# 1_P1_schdoc.net
KiCad netlist of a schematic drawn in Altium Designer
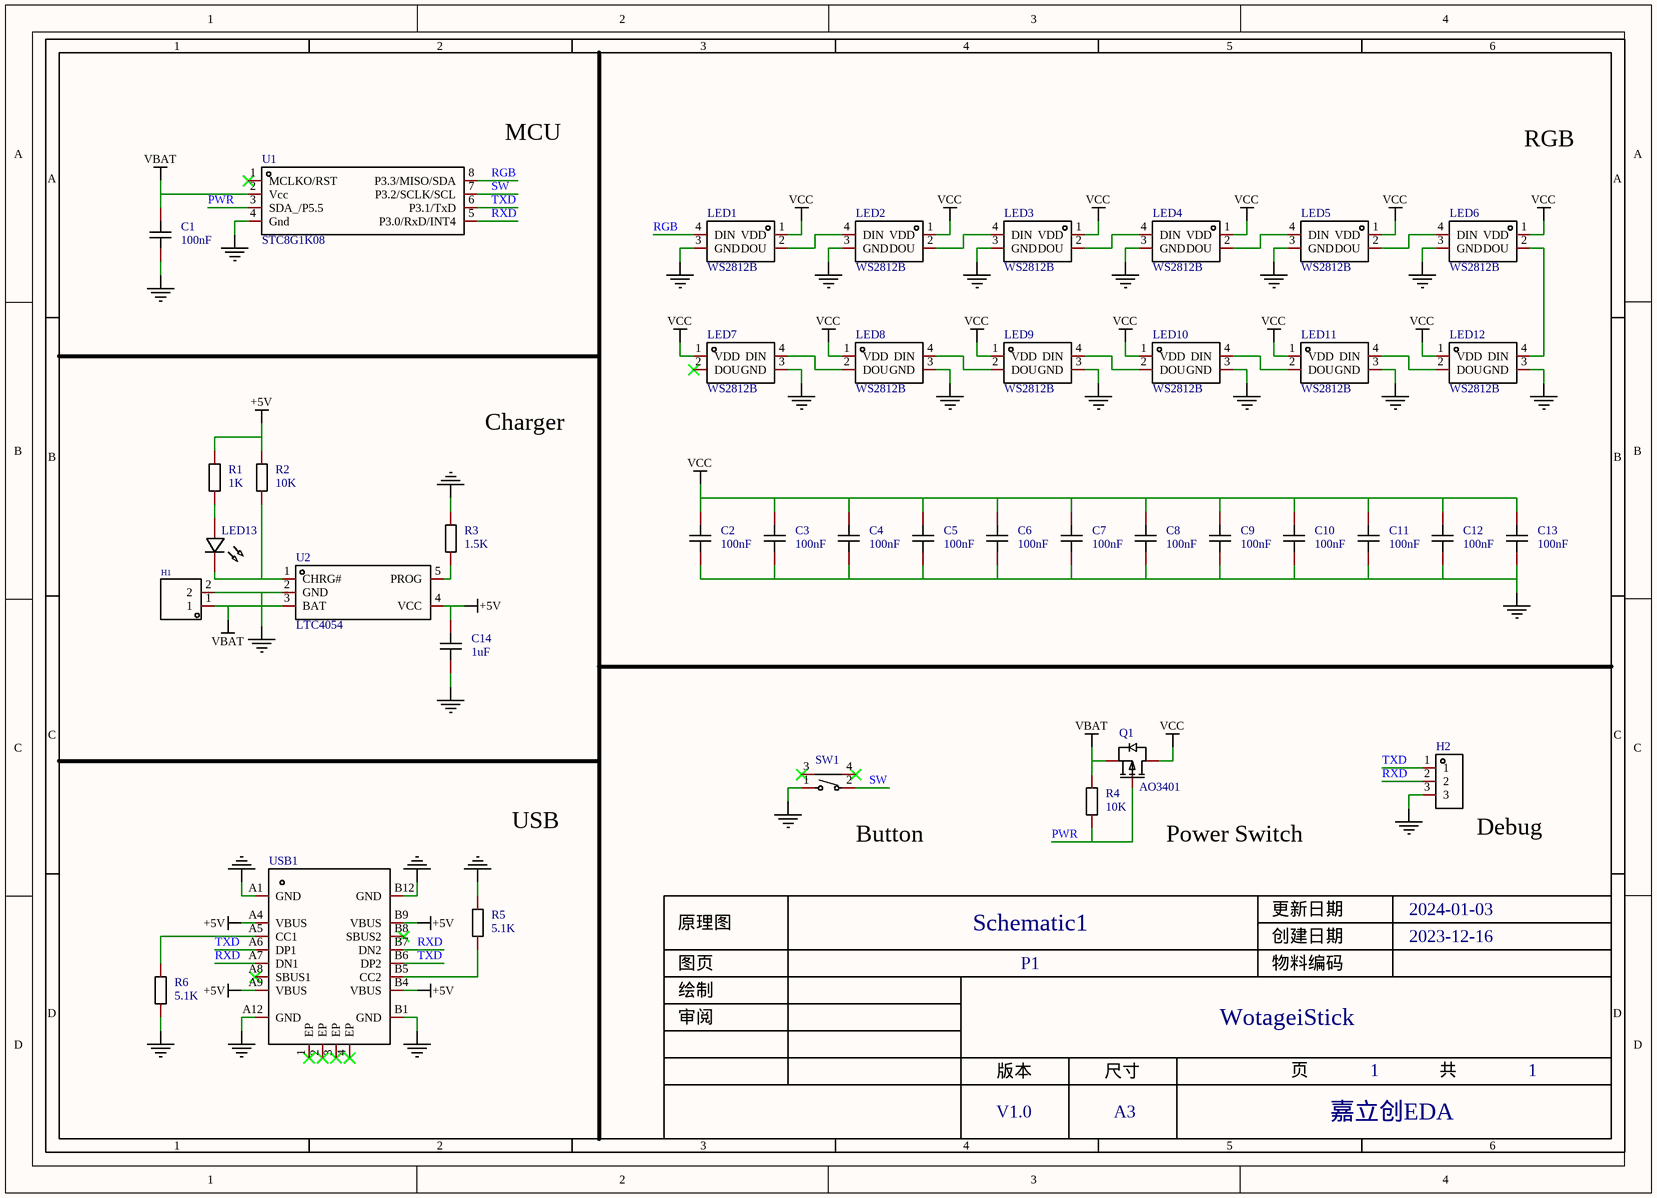
[diagram p0: 1_P1.schdoc.schdoc]

(export (version "E")
  (design (tool "Eeschema 10.0.6"))
  (components
    (comp (ref "C1")
      (value "100nF")
      (fields (field (name "NAME") "100nF"))
      (libsource (lib "altium-import") (part "root_1_CAP_0603_"))
    )
    (comp (ref "C2")
      (value "100nF")
      (fields (field (name "NAME") "100nF"))
      (libsource (lib "altium-import") (part "root_1_CAP_0603_"))
    )
    (comp (ref "C3")
      (value "100nF")
      (fields (field (name "NAME") "100nF"))
      (libsource (lib "altium-import") (part "root_1_CAP_0603_"))
    )
    (comp (ref "C4")
      (value "100nF")
      (fields (field (name "NAME") "100nF"))
      (libsource (lib "altium-import") (part "root_1_CAP_0603_"))
    )
    (comp (ref "C5")
      (value "100nF")
      (fields (field (name "NAME") "100nF"))
      (libsource (lib "altium-import") (part "root_1_CAP_0603_"))
    )
    (comp (ref "C6")
      (value "100nF")
      (fields (field (name "NAME") "100nF"))
      (libsource (lib "altium-import") (part "root_1_CAP_0603_"))
    )
    (comp (ref "C7")
      (value "100nF")
      (fields (field (name "NAME") "100nF"))
      (libsource (lib "altium-import") (part "root_1_CAP_0603_"))
    )
    (comp (ref "C8")
      (value "100nF")
      (fields (field (name "NAME") "100nF"))
      (libsource (lib "altium-import") (part "root_1_CAP_0603_"))
    )
    (comp (ref "C9")
      (value "100nF")
      (fields (field (name "NAME") "100nF"))
      (libsource (lib "altium-import") (part "root_1_CAP_0603_"))
    )
    (comp (ref "C10")
      (value "100nF")
      (fields (field (name "NAME") "100nF"))
      (libsource (lib "altium-import") (part "root_1_CAP_0603_"))
    )
    (comp (ref "C11")
      (value "100nF")
      (fields (field (name "NAME") "100nF"))
      (libsource (lib "altium-import") (part "root_1_CAP_0603_"))
    )
    (comp (ref "C12")
      (value "100nF")
      (fields (field (name "NAME") "100nF"))
      (libsource (lib "altium-import") (part "root_1_CAP_0603_"))
    )
    (comp (ref "C13")
      (value "100nF")
      (fields (field (name "NAME") "100nF"))
      (libsource (lib "altium-import") (part "root_1_CAP_0603_"))
    )
    (comp (ref "C14")
      (value "1uF")
      (fields (field (name "NAME") "1uF"))
      (libsource (lib "altium-import") (part "root_1_CAP_0603_"))
    )
    (comp (ref "H1")
      (value "HDR-M_2.54_1x2P")
      (fields (field (name "MANUFACTURER") "Ckmtw(灿科盟)") (field (name "MANUFACTURER PART") "B-2100S02P-A110"))
      (libsource (lib "altium-import") (part "root_2_HDR-M_2.54_1x2P_"))
    )
    (comp (ref "H2")
      (value "HDR-M_2.54_1x3P")
      (libsource (lib "altium-import") (part "root_0_HDR-M_2.54_1x3P_"))
    )
    (comp (ref "LED1")
      (value "WS2812B")
      (description "发光颜色:RGB三色;二极管配置:-;功率:-;透镜颜色:无色透明透镜;主波长:-;色温:-;发光角度:120°;安装方式:正贴;工作温度:-30℃~+70℃;")
      (fields (field (name "NAME") "WS2812B") (field (name "MANUFACTURER") "XINGLIGHT(成兴光)"))
      (libsource (lib "altium-import") (part "root_0_mirrored_XL-5050RGBC-WS2812B_"))
    )
    (comp (ref "LED2")
      (value "WS2812B")
      (description "发光颜色:RGB三色;二极管配置:-;功率:-;透镜颜色:无色透明透镜;主波长:-;色温:-;发光角度:120°;安装方式:正贴;工作温度:-30℃~+70℃;")
      (fields (field (name "NAME") "WS2812B") (field (name "MANUFACTURER") "XINGLIGHT(成兴光)"))
      (libsource (lib "altium-import") (part "root_0_mirrored_XL-5050RGBC-WS2812B_"))
    )
    (comp (ref "LED3")
      (value "WS2812B")
      (description "发光颜色:RGB三色;二极管配置:-;功率:-;透镜颜色:无色透明透镜;主波长:-;色温:-;发光角度:120°;安装方式:正贴;工作温度:-30℃~+70℃;")
      (fields (field (name "NAME") "WS2812B") (field (name "MANUFACTURER") "XINGLIGHT(成兴光)"))
      (libsource (lib "altium-import") (part "root_0_mirrored_XL-5050RGBC-WS2812B_"))
    )
    (comp (ref "LED4")
      (value "WS2812B")
      (description "发光颜色:RGB三色;二极管配置:-;功率:-;透镜颜色:无色透明透镜;主波长:-;色温:-;发光角度:120°;安装方式:正贴;工作温度:-30℃~+70℃;")
      (fields (field (name "NAME") "WS2812B") (field (name "MANUFACTURER") "XINGLIGHT(成兴光)"))
      (libsource (lib "altium-import") (part "root_0_mirrored_XL-5050RGBC-WS2812B_"))
    )
    (comp (ref "LED5")
      (value "WS2812B")
      (description "发光颜色:RGB三色;二极管配置:-;功率:-;透镜颜色:无色透明透镜;主波长:-;色温:-;发光角度:120°;安装方式:正贴;工作温度:-30℃~+70℃;")
      (fields (field (name "NAME") "WS2812B") (field (name "MANUFACTURER") "XINGLIGHT(成兴光)"))
      (libsource (lib "altium-import") (part "root_0_mirrored_XL-5050RGBC-WS2812B_"))
    )
    (comp (ref "LED6")
      (value "WS2812B")
      (description "发光颜色:RGB三色;二极管配置:-;功率:-;透镜颜色:无色透明透镜;主波长:-;色温:-;发光角度:120°;安装方式:正贴;工作温度:-30℃~+70℃;")
      (fields (field (name "NAME") "WS2812B") (field (name "MANUFACTURER") "XINGLIGHT(成兴光)"))
      (libsource (lib "altium-import") (part "root_0_mirrored_XL-5050RGBC-WS2812B_"))
    )
    (comp (ref "LED7")
      (value "WS2812B")
      (description "发光颜色:RGB三色;二极管配置:-;功率:-;透镜颜色:无色透明透镜;主波长:-;色温:-;发光角度:120°;安装方式:正贴;工作温度:-30℃~+70℃;")
      (fields (field (name "NAME") "WS2812B") (field (name "MANUFACTURER") "XINGLIGHT(成兴光)"))
      (libsource (lib "altium-import") (part "root_0_XL-5050RGBC-WS2812B_"))
    )
    (comp (ref "LED8")
      (value "WS2812B")
      (description "发光颜色:RGB三色;二极管配置:-;功率:-;透镜颜色:无色透明透镜;主波长:-;色温:-;发光角度:120°;安装方式:正贴;工作温度:-30℃~+70℃;")
      (fields (field (name "NAME") "WS2812B") (field (name "MANUFACTURER") "XINGLIGHT(成兴光)"))
      (libsource (lib "altium-import") (part "root_0_XL-5050RGBC-WS2812B_"))
    )
    (comp (ref "LED9")
      (value "WS2812B")
      (description "发光颜色:RGB三色;二极管配置:-;功率:-;透镜颜色:无色透明透镜;主波长:-;色温:-;发光角度:120°;安装方式:正贴;工作温度:-30℃~+70℃;")
      (fields (field (name "NAME") "WS2812B") (field (name "MANUFACTURER") "XINGLIGHT(成兴光)"))
      (libsource (lib "altium-import") (part "root_0_XL-5050RGBC-WS2812B_"))
    )
    (comp (ref "LED10")
      (value "WS2812B")
      (description "发光颜色:RGB三色;二极管配置:-;功率:-;透镜颜色:无色透明透镜;主波长:-;色温:-;发光角度:120°;安装方式:正贴;工作温度:-30℃~+70℃;")
      (fields (field (name "NAME") "WS2812B") (field (name "MANUFACTURER") "XINGLIGHT(成兴光)"))
      (libsource (lib "altium-import") (part "root_0_XL-5050RGBC-WS2812B_"))
    )
    (comp (ref "LED11")
      (value "WS2812B")
      (description "发光颜色:RGB三色;二极管配置:-;功率:-;透镜颜色:无色透明透镜;主波长:-;色温:-;发光角度:120°;安装方式:正贴;工作温度:-30℃~+70℃;")
      (fields (field (name "NAME") "WS2812B") (field (name "MANUFACTURER") "XINGLIGHT(成兴光)"))
      (libsource (lib "altium-import") (part "root_0_XL-5050RGBC-WS2812B_"))
    )
    (comp (ref "LED12")
      (value "WS2812B")
      (description "发光颜色:RGB三色;二极管配置:-;功率:-;透镜颜色:无色透明透镜;主波长:-;色温:-;发光角度:120°;安装方式:正贴;工作温度:-30℃~+70℃;")
      (fields (field (name "NAME") "WS2812B") (field (name "MANUFACTURER") "XINGLIGHT(成兴光)"))
      (libsource (lib "altium-import") (part "root_0_XL-5050RGBC-WS2812B_"))
    )
    (comp (ref "LED13") (value "LED_0603-R") (libsource (lib "altium-import") (part "root_3_LED_0603-R_")))
    (comp (ref "Q1")
      (value "AO3401")
      (fields (field (name "NAME") "AO3401"))
      (libsource (lib "altium-import") (part "root_1_mirrored_AO3401A_P_"))
    )
    (comp (ref "R1")
      (value "1K")
      (fields (field (name "NAME") "1K"))
      (libsource (lib "altium-import") (part "root_3_Res_0603_"))
    )
    (comp (ref "R2")
      (value "10K")
      (fields (field (name "NAME") "10K"))
      (libsource (lib "altium-import") (part "root_3_Res_0603_"))
    )
    (comp (ref "R3")
      (value "1.5K")
      (fields (field (name "NAME") "1.5K"))
      (libsource (lib "altium-import") (part "root_3_Res_0603_"))
    )
    (comp (ref "R4")
      (value "10K")
      (fields (field (name "NAME") "10K"))
      (libsource (lib "altium-import") (part "root_1_Res_0603_"))
    )
    (comp (ref "R5")
      (value "5.1K")
      (fields (field (name "NAME") "5.1K"))
      (libsource (lib "altium-import") (part "root_3_Res_0603_"))
    )
    (comp (ref "R6")
      (value "5.1K")
      (fields (field (name "NAME") "5.1K"))
      (libsource (lib "altium-import") (part "root_1_Res_0603_"))
    )
    (comp (ref "SW1")
      (value "TS-KG86E-ACT35F")
      (description "触点电流:50mA;额定电压(DC):12V;绝缘电阻:100MΩ;机械寿命:-;")
      (fields (field (name "MANUFACTURER") "HANBO(汉博)"))
      (libsource (lib "altium-import") (part "root_0_TS-KG86E-ACT35F_"))
    )
    (comp (ref "U1")
      (value "STC8G1K08")
      (description "CPU内核:51系列;CPU最大主频:-;程序存储容量:8KB;程序存储器类型:FLASH;GPIO端口数量:6;工作电压范围:1.9V~5.5V;RAM总容量:1.25KB;")
      (fields (field (name "NAME") "STC8G1K08") (field (name "MANUFACTURER") "STC(宏晶)"))
      (libsource (lib "altium-import") (part "root_0_STC8G1K08-36I-SOP8_"))
    )
    (comp (ref "U2")
      (value "LTC4054")
      (description "具有热调节功能的独立线性锂离子电池充电器")
      (fields (field (name "NAME") "LTC4054") (field (name "MANUFACTURER") "ADI(亚德诺)/LINEAR(凌特)"))
      (libsource (lib "altium-import") (part "root_0_LTC4054ES5-4.2#PBF_"))
    )
    (comp (ref "USB1")
      (value "USB_TYPE-C-16P")
      (libsource (lib "altium-import") (part "root_0_USB_TYPE-C-16P_"))
    )
  )
  (nets
    (net (code "1") (name "+5V") (class "Default")
      (node (ref "C14") (pin "2") (pinfunction "2_2") (pintype "passive"))
      (node (ref "R1") (pin "1") (pinfunction "1_1") (pintype "passive"))
      (node (ref "R2") (pin "1") (pinfunction "1_1") (pintype "passive"))
      (node (ref "U2") (pin "4") (pinfunction "VCC_4") (pintype "passive"))
      (node (ref "USB1") (pin "A4") (pinfunction "VBUS_A4") (pintype "passive"))
      (node (ref "USB1") (pin "A9") (pinfunction "VBUS_A9") (pintype "passive"))
      (node (ref "USB1") (pin "B4") (pinfunction "VBUS_B4") (pintype "passive"))
      (node (ref "USB1") (pin "B9") (pinfunction "VBUS_B9") (pintype "passive"))
    )
    (net (code "2") (name "/PWR") (class "Default")
      (node (ref "Q1") (pin "1") (pinfunction "G_1") (pintype "passive"))
      (node (ref "R4") (pin "1") (pinfunction "1_1") (pintype "passive"))
      (node (ref "U1") (pin "3") (pinfunction "SDA_/P5.5_3") (pintype "passive"))
    )
    (net (code "3") (name "/RGB") (class "Default")
      (node (ref "LED1") (pin "4") (pinfunction "DIN_4") (pintype "passive"))
      (node (ref "U1") (pin "8") (pinfunction "P3.3/MISO/SDA_8") (pintype "passive"))
    )
    (net (code "4") (name "/RXD") (class "Default")
      (node (ref "H2") (pin "2") (pinfunction "2_2") (pintype "passive"))
      (node (ref "U1") (pin "5") (pinfunction "P3.0/RxD/INT4_5") (pintype "passive"))
      (node (ref "USB1") (pin "A7") (pinfunction "DN1_A7") (pintype "passive"))
      (node (ref "USB1") (pin "B7") (pinfunction "DN2_B7") (pintype "passive"))
    )
    (net (code "5") (name "/SW") (class "Default")
      (node (ref "SW1") (pin "2") (pinfunction "2_2") (pintype "passive"))
      (node (ref "U1") (pin "7") (pinfunction "P3.2/SCLK/SCL_7") (pintype "passive"))
    )
    (net (code "6") (name "/TXD") (class "Default")
      (node (ref "H2") (pin "1") (pinfunction "1_1") (pintype "passive"))
      (node (ref "U1") (pin "6") (pinfunction "P3.1/TxD_6") (pintype "passive"))
      (node (ref "USB1") (pin "A6") (pinfunction "DP1_A6") (pintype "passive"))
      (node (ref "USB1") (pin "B6") (pinfunction "DP2_B6") (pintype "passive"))
    )
    (net (code "7") (name "<NO NET>") (class "Default")
      (node (ref "C1") (pin "1") (pinfunction "1_1") (pintype "passive"))
      (node (ref "C10") (pin "1") (pinfunction "1_1") (pintype "passive"))
      (node (ref "C11") (pin "1") (pinfunction "1_1") (pintype "passive"))
      (node (ref "C12") (pin "1") (pinfunction "1_1") (pintype "passive"))
      (node (ref "C13") (pin "1") (pinfunction "1_1") (pintype "passive"))
      (node (ref "C14") (pin "1") (pinfunction "1_1") (pintype "passive"))
      (node (ref "C2") (pin "1") (pinfunction "1_1") (pintype "passive"))
      (node (ref "C3") (pin "1") (pinfunction "1_1") (pintype "passive"))
      (node (ref "C4") (pin "1") (pinfunction "1_1") (pintype "passive"))
      (node (ref "C5") (pin "1") (pinfunction "1_1") (pintype "passive"))
      (node (ref "C6") (pin "1") (pinfunction "1_1") (pintype "passive"))
      (node (ref "C7") (pin "1") (pinfunction "1_1") (pintype "passive"))
      (node (ref "C8") (pin "1") (pinfunction "1_1") (pintype "passive"))
      (node (ref "C9") (pin "1") (pinfunction "1_1") (pintype "passive"))
      (node (ref "H1") (pin "2") (pinfunction "2_2") (pintype "passive"))
      (node (ref "H2") (pin "3") (pinfunction "3_3") (pintype "passive"))
      (node (ref "LED1") (pin "3") (pinfunction "GND_3") (pintype "passive"))
      (node (ref "LED10") (pin "3") (pinfunction "GND_3") (pintype "passive"))
      (node (ref "LED11") (pin "3") (pinfunction "GND_3") (pintype "passive"))
      (node (ref "LED12") (pin "3") (pinfunction "GND_3") (pintype "passive"))
      (node (ref "LED2") (pin "3") (pinfunction "GND_3") (pintype "passive"))
      (node (ref "LED3") (pin "3") (pinfunction "GND_3") (pintype "passive"))
      (node (ref "LED4") (pin "3") (pinfunction "GND_3") (pintype "passive"))
      (node (ref "LED5") (pin "3") (pinfunction "GND_3") (pintype "passive"))
      (node (ref "LED6") (pin "3") (pinfunction "GND_3") (pintype "passive"))
      (node (ref "LED7") (pin "3") (pinfunction "GND_3") (pintype "passive"))
      (node (ref "LED8") (pin "3") (pinfunction "GND_3") (pintype "passive"))
      (node (ref "LED9") (pin "3") (pinfunction "GND_3") (pintype "passive"))
      (node (ref "R3") (pin "1") (pinfunction "1_1") (pintype "passive"))
      (node (ref "R5") (pin "1") (pinfunction "1_1") (pintype "passive"))
      (node (ref "R6") (pin "1") (pinfunction "1_1") (pintype "passive"))
      (node (ref "SW1") (pin "1") (pinfunction "1_1") (pintype "passive"))
      (node (ref "U1") (pin "4") (pinfunction "Gnd_4") (pintype "passive"))
      (node (ref "U2") (pin "2") (pinfunction "GND_2") (pintype "passive"))
      (node (ref "USB1") (pin "A1") (pinfunction "GND_A1") (pintype "passive"))
      (node (ref "USB1") (pin "A12") (pinfunction "GND_A12") (pintype "passive"))
      (node (ref "USB1") (pin "B1") (pinfunction "GND_B1") (pintype "passive"))
      (node (ref "USB1") (pin "B12") (pinfunction "GND_B12") (pintype "passive"))
    )
    (net (code "8") (name "Net-(LED1-DOU)") (class "Default")
      (node (ref "LED1") (pin "2") (pinfunction "DOU_2") (pintype "passive"))
      (node (ref "LED2") (pin "4") (pinfunction "DIN_4") (pintype "passive"))
    )
    (net (code "9") (name "Net-(LED2-DOU)") (class "Default")
      (node (ref "LED2") (pin "2") (pinfunction "DOU_2") (pintype "passive"))
      (node (ref "LED3") (pin "4") (pinfunction "DIN_4") (pintype "passive"))
    )
    (net (code "10") (name "Net-(LED3-DOU)") (class "Default")
      (node (ref "LED3") (pin "2") (pinfunction "DOU_2") (pintype "passive"))
      (node (ref "LED4") (pin "4") (pinfunction "DIN_4") (pintype "passive"))
    )
    (net (code "11") (name "Net-(LED4-DOU)") (class "Default")
      (node (ref "LED4") (pin "2") (pinfunction "DOU_2") (pintype "passive"))
      (node (ref "LED5") (pin "4") (pinfunction "DIN_4") (pintype "passive"))
    )
    (net (code "12") (name "Net-(LED5-DOU)") (class "Default")
      (node (ref "LED5") (pin "2") (pinfunction "DOU_2") (pintype "passive"))
      (node (ref "LED6") (pin "4") (pinfunction "DIN_4") (pintype "passive"))
    )
    (net (code "13") (name "Net-(LED7-DIN)") (class "Default")
      (node (ref "LED7") (pin "4") (pinfunction "DIN_4") (pintype "passive"))
      (node (ref "LED8") (pin "2") (pinfunction "DOU_2") (pintype "passive"))
    )
    (net (code "14") (name "Net-(LED8-DIN)") (class "Default")
      (node (ref "LED8") (pin "4") (pinfunction "DIN_4") (pintype "passive"))
      (node (ref "LED9") (pin "2") (pinfunction "DOU_2") (pintype "passive"))
    )
    (net (code "15") (name "Net-(LED10-DIN)") (class "Default")
      (node (ref "LED10") (pin "4") (pinfunction "DIN_4") (pintype "passive"))
      (node (ref "LED11") (pin "2") (pinfunction "DOU_2") (pintype "passive"))
    )
    (net (code "16") (name "Net-(LED10-DOU)") (class "Default")
      (node (ref "LED10") (pin "2") (pinfunction "DOU_2") (pintype "passive"))
      (node (ref "LED9") (pin "4") (pinfunction "DIN_4") (pintype "passive"))
    )
    (net (code "17") (name "Net-(LED11-DIN)") (class "Default")
      (node (ref "LED11") (pin "4") (pinfunction "DIN_4") (pintype "passive"))
      (node (ref "LED12") (pin "2") (pinfunction "DOU_2") (pintype "passive"))
    )
    (net (code "18") (name "Net-(LED12-DIN)") (class "Default")
      (node (ref "LED12") (pin "4") (pinfunction "DIN_4") (pintype "passive"))
      (node (ref "LED6") (pin "2") (pinfunction "DOU_2") (pintype "passive"))
    )
    (net (code "19") (name "Net-(LED13-A)") (class "Default")
      (node (ref "LED13") (pin "2") (pinfunction "A_2") (pintype "passive"))
      (node (ref "R1") (pin "2") (pinfunction "2_2") (pintype "passive"))
    )
    (net (code "20") (name "Net-(LED13-C)") (class "Default")
      (node (ref "LED13") (pin "1") (pinfunction "C_1") (pintype "passive"))
      (node (ref "R2") (pin "2") (pinfunction "2_2") (pintype "passive"))
      (node (ref "U2") (pin "1") (pinfunction "CHRG#_1") (pintype "passive"))
    )
    (net (code "21") (name "Net-(U2-PROG)") (class "Default")
      (node (ref "R3") (pin "2") (pinfunction "2_2") (pintype "passive"))
      (node (ref "U2") (pin "5") (pinfunction "PROG_5") (pintype "passive"))
    )
    (net (code "22") (name "Net-(USB1-CC1)") (class "Default")
      (node (ref "R6") (pin "2") (pinfunction "2_2") (pintype "passive"))
      (node (ref "USB1") (pin "A5") (pinfunction "CC1_A5") (pintype "passive"))
    )
    (net (code "23") (name "Net-(USB1-CC2)") (class "Default")
      (node (ref "R5") (pin "2") (pinfunction "2_2") (pintype "passive"))
      (node (ref "USB1") (pin "B5") (pinfunction "CC2_B5") (pintype "passive"))
    )
    (net (code "24") (name "VBAT") (class "Default")
      (node (ref "C1") (pin "2") (pinfunction "2_2") (pintype "passive"))
      (node (ref "H1") (pin "1") (pinfunction "1_1") (pintype "passive"))
      (node (ref "Q1") (pin "2") (pinfunction "S_2") (pintype "passive"))
      (node (ref "R4") (pin "2") (pinfunction "2_2") (pintype "passive"))
      (node (ref "U1") (pin "2") (pinfunction "Vcc_2") (pintype "passive"))
      (node (ref "U2") (pin "3") (pinfunction "BAT_3") (pintype "passive"))
    )
    (net (code "25") (name "VCC") (class "Default")
      (node (ref "C10") (pin "2") (pinfunction "2_2") (pintype "passive"))
      (node (ref "C11") (pin "2") (pinfunction "2_2") (pintype "passive"))
      (node (ref "C12") (pin "2") (pinfunction "2_2") (pintype "passive"))
      (node (ref "C13") (pin "2") (pinfunction "2_2") (pintype "passive"))
      (node (ref "C2") (pin "2") (pinfunction "2_2") (pintype "passive"))
      (node (ref "C3") (pin "2") (pinfunction "2_2") (pintype "passive"))
      (node (ref "C4") (pin "2") (pinfunction "2_2") (pintype "passive"))
      (node (ref "C5") (pin "2") (pinfunction "2_2") (pintype "passive"))
      (node (ref "C6") (pin "2") (pinfunction "2_2") (pintype "passive"))
      (node (ref "C7") (pin "2") (pinfunction "2_2") (pintype "passive"))
      (node (ref "C8") (pin "2") (pinfunction "2_2") (pintype "passive"))
      (node (ref "C9") (pin "2") (pinfunction "2_2") (pintype "passive"))
      (node (ref "LED1") (pin "1") (pinfunction "VDD_1") (pintype "passive"))
      (node (ref "LED10") (pin "1") (pinfunction "VDD_1") (pintype "passive"))
      (node (ref "LED11") (pin "1") (pinfunction "VDD_1") (pintype "passive"))
      (node (ref "LED12") (pin "1") (pinfunction "VDD_1") (pintype "passive"))
      (node (ref "LED2") (pin "1") (pinfunction "VDD_1") (pintype "passive"))
      (node (ref "LED3") (pin "1") (pinfunction "VDD_1") (pintype "passive"))
      (node (ref "LED4") (pin "1") (pinfunction "VDD_1") (pintype "passive"))
      (node (ref "LED5") (pin "1") (pinfunction "VDD_1") (pintype "passive"))
      (node (ref "LED6") (pin "1") (pinfunction "VDD_1") (pintype "passive"))
      (node (ref "LED7") (pin "1") (pinfunction "VDD_1") (pintype "passive"))
      (node (ref "LED8") (pin "1") (pinfunction "VDD_1") (pintype "passive"))
      (node (ref "LED9") (pin "1") (pinfunction "VDD_1") (pintype "passive"))
      (node (ref "Q1") (pin "3") (pinfunction "D_3") (pintype "passive"))
    )
    (net (code "26") (name "unconnected-(LED7-DOU-Pad2)") (class "Default")
      (node (ref "LED7") (pin "2") (pinfunction "DOU_2") (pintype "passive+no_connect"))
    )
    (net (code "27") (name "unconnected-(SW1-Pad3)") (class "Default")
      (node (ref "SW1") (pin "3") (pinfunction "3_3") (pintype "passive+no_connect"))
    )
    (net (code "28") (name "unconnected-(SW1-Pad4)") (class "Default")
      (node (ref "SW1") (pin "4") (pinfunction "4_4") (pintype "passive+no_connect"))
    )
    (net (code "29") (name "unconnected-(U1-MCLKO{slash}RST-Pad1)") (class "Default")
      (node (ref "U1") (pin "1") (pinfunction "MCLKO/RST_1") (pintype "passive+no_connect"))
    )
    (net (code "30") (name "unconnected-(USB1-EP-Pad1)") (class "Default")
      (node (ref "USB1") (pin "1") (pinfunction "EP_1") (pintype "passive+no_connect"))
    )
    (net (code "31") (name "unconnected-(USB1-EP-Pad2)") (class "Default")
      (node (ref "USB1") (pin "2") (pinfunction "EP_2") (pintype "passive+no_connect"))
    )
    (net (code "32") (name "unconnected-(USB1-EP-Pad3)") (class "Default")
      (node (ref "USB1") (pin "3") (pinfunction "EP_3") (pintype "passive+no_connect"))
    )
    (net (code "33") (name "unconnected-(USB1-EP-Pad4)") (class "Default")
      (node (ref "USB1") (pin "4") (pinfunction "EP_4") (pintype "passive+no_connect"))
    )
    (net (code "34") (name "unconnected-(USB1-SBUS1-PadA8)") (class "Default")
      (node (ref "USB1") (pin "A8") (pinfunction "SBUS1_A8") (pintype "passive+no_connect"))
    )
    (net (code "35") (name "unconnected-(USB1-SBUS2-PadB8)") (class "Default")
      (node (ref "USB1") (pin "B8") (pinfunction "SBUS2_B8") (pintype "passive+no_connect"))
    )
  )
)
